# Lighting.net
KiCad netlist of a schematic drawn in EAGLE
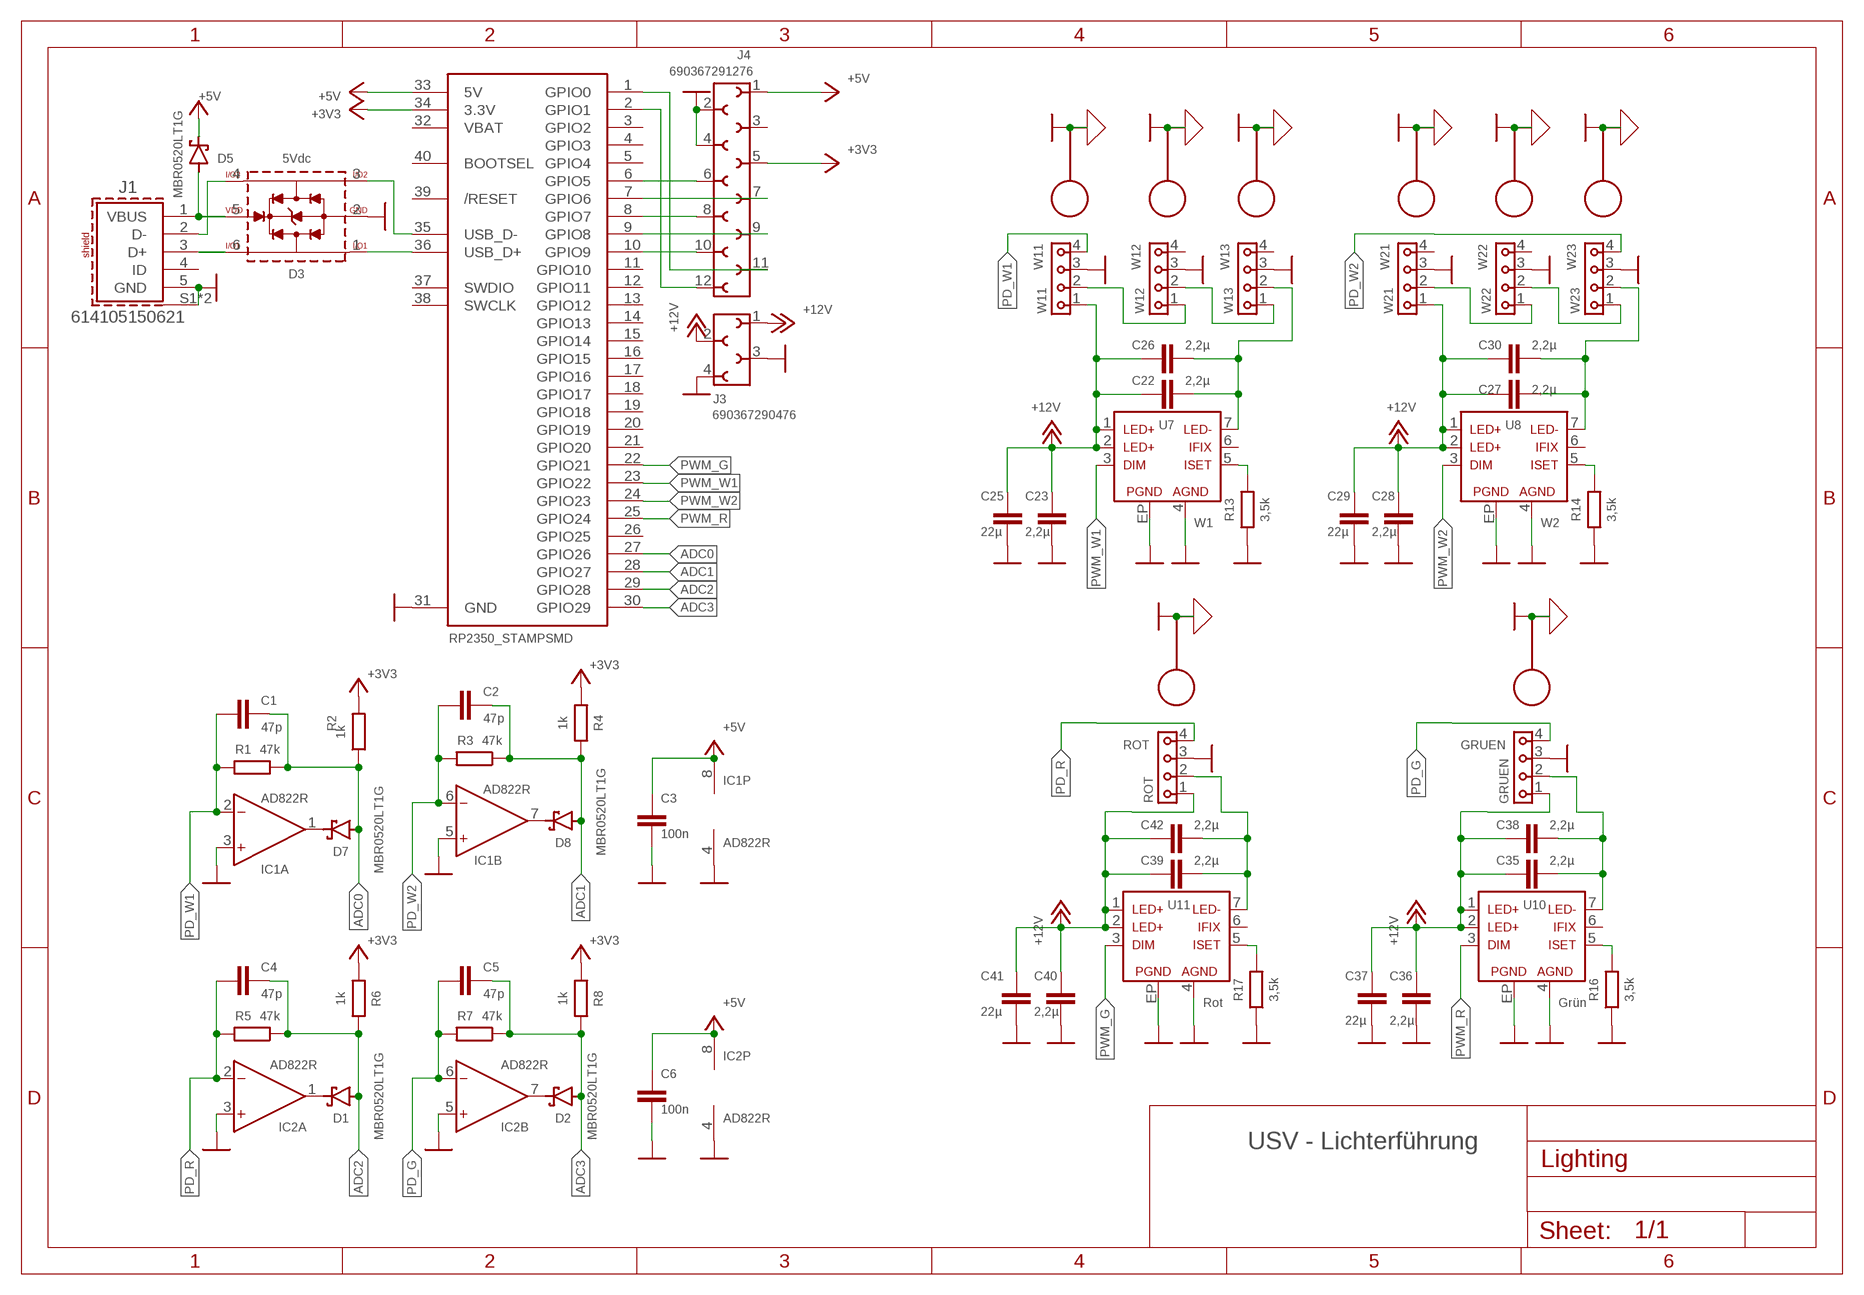
[diagram p0: schematic, sheet 1]

(export (version "E")
  (design (tool "Eeschema 10.0.6"))
  (components
    (comp (ref "C1")
      (value "47p")
      (footprint "eagle-import:CAPC2012X110")
      (libsource (lib "eagle-import") (part "CCHIP-0805(2012-METRIC)_"))
    )
    (comp (ref "C2")
      (value "47p")
      (footprint "eagle-import:CAPC2012X110")
      (libsource (lib "eagle-import") (part "CCHIP-0805(2012-METRIC)_"))
    )
    (comp (ref "C3")
      (value "100n")
      (footprint "eagle-import:CAPC2012X110")
      (libsource (lib "eagle-import") (part "CCHIP-0805(2012-METRIC)_"))
    )
    (comp (ref "C4")
      (value "47p")
      (footprint "eagle-import:CAPC2012X110")
      (libsource (lib "eagle-import") (part "CCHIP-0805(2012-METRIC)_"))
    )
    (comp (ref "C5")
      (value "47p")
      (footprint "eagle-import:CAPC2012X110")
      (libsource (lib "eagle-import") (part "CCHIP-0805(2012-METRIC)_"))
    )
    (comp (ref "C6")
      (value "100n")
      (footprint "eagle-import:CAPC2012X110")
      (libsource (lib "eagle-import") (part "CCHIP-0805(2012-METRIC)_"))
    )
    (comp (ref "C22")
      (value "2,2µ")
      (footprint "eagle-import:CAPC2012X110")
      (libsource (lib "eagle-import") (part "CCHIP-0805(2012-METRIC)_"))
    )
    (comp (ref "C23")
      (value "2,2µ")
      (footprint "eagle-import:CAPC2012X110")
      (libsource (lib "eagle-import") (part "CCHIP-0805(2012-METRIC)_"))
    )
    (comp (ref "C25")
      (value "22µ")
      (footprint "eagle-import:CAPC2012X110")
      (libsource (lib "eagle-import") (part "CCHIP-0805(2012-METRIC)_"))
    )
    (comp (ref "C26")
      (value "2,2µ")
      (footprint "eagle-import:CAPC2012X110")
      (libsource (lib "eagle-import") (part "CCHIP-0805(2012-METRIC)_"))
    )
    (comp (ref "C27")
      (value "2,2µ")
      (footprint "eagle-import:CAPC2012X110")
      (libsource (lib "eagle-import") (part "CCHIP-0805(2012-METRIC)_"))
    )
    (comp (ref "C28")
      (value "2,2µ")
      (footprint "eagle-import:CAPC2012X110")
      (libsource (lib "eagle-import") (part "CCHIP-0805(2012-METRIC)_"))
    )
    (comp (ref "C29")
      (value "22µ")
      (footprint "eagle-import:CAPC2012X110")
      (libsource (lib "eagle-import") (part "CCHIP-0805(2012-METRIC)_"))
    )
    (comp (ref "C30")
      (value "2,2µ")
      (footprint "eagle-import:CAPC2012X110")
      (libsource (lib "eagle-import") (part "CCHIP-0805(2012-METRIC)_"))
    )
    (comp (ref "C35")
      (value "2,2µ")
      (footprint "eagle-import:CAPC2012X110")
      (libsource (lib "eagle-import") (part "CCHIP-0805(2012-METRIC)_"))
    )
    (comp (ref "C36")
      (value "2,2µ")
      (footprint "eagle-import:CAPC2012X110")
      (libsource (lib "eagle-import") (part "CCHIP-0805(2012-METRIC)_"))
    )
    (comp (ref "C37")
      (value "22µ")
      (footprint "eagle-import:CAPC2012X110")
      (libsource (lib "eagle-import") (part "CCHIP-0805(2012-METRIC)_"))
    )
    (comp (ref "C38")
      (value "2,2µ")
      (footprint "eagle-import:CAPC2012X110")
      (libsource (lib "eagle-import") (part "CCHIP-0805(2012-METRIC)_"))
    )
    (comp (ref "C39")
      (value "2,2µ")
      (footprint "eagle-import:CAPC2012X110")
      (libsource (lib "eagle-import") (part "CCHIP-0805(2012-METRIC)_"))
    )
    (comp (ref "C40")
      (value "2,2µ")
      (footprint "eagle-import:CAPC2012X110")
      (libsource (lib "eagle-import") (part "CCHIP-0805(2012-METRIC)_"))
    )
    (comp (ref "C41")
      (value "22µ")
      (footprint "eagle-import:CAPC2012X110")
      (libsource (lib "eagle-import") (part "CCHIP-0805(2012-METRIC)_"))
    )
    (comp (ref "C42")
      (value "2,2µ")
      (footprint "eagle-import:CAPC2012X110")
      (libsource (lib "eagle-import") (part "CCHIP-0805(2012-METRIC)_"))
    )
    (comp (ref "D1")
      (value "MBR0520LT1G")
      (footprint "eagle-import:SODFL3718X115")
      (fields (field (name "MANUFACTURER") "ON Semiconductor"))
      (libsource (lib "eagle-import") (part "SCHOTTKY_DO-219MBR0520LT1G"))
    )
    (comp (ref "D2")
      (value "MBR0520LT1G")
      (footprint "eagle-import:SODFL3718X115")
      (fields (field (name "MANUFACTURER") "ON Semiconductor"))
      (libsource (lib "eagle-import") (part "SCHOTTKY_DO-219MBR0520LT1G"))
    )
    (comp (ref "D3")
      (value "5Vdc")
      (footprint "eagle-import:WE-TVS_SOT563")
      (libsource (lib "eagle-import") (part "WE-TVS-HS_SOT563_82400152"))
    )
    (comp (ref "D5")
      (value "MBR0520LT1G")
      (footprint "eagle-import:SODFL3718X115")
      (fields (field (name "MANUFACTURER") "ON Semiconductor"))
      (libsource (lib "eagle-import") (part "SCHOTTKY_DO-219MBR0520LT1G"))
    )
    (comp (ref "D7")
      (value "MBR0520LT1G")
      (footprint "eagle-import:SODFL3718X115")
      (fields (field (name "MANUFACTURER") "ON Semiconductor"))
      (libsource (lib "eagle-import") (part "SCHOTTKY_DO-219MBR0520LT1G"))
    )
    (comp (ref "D8")
      (value "MBR0520LT1G")
      (footprint "eagle-import:SODFL3718X115")
      (fields (field (name "MANUFACTURER") "ON Semiconductor"))
      (libsource (lib "eagle-import") (part "SCHOTTKY_DO-219MBR0520LT1G"))
    )
    (comp (ref "GRUEN")
      (value "GRUEN")
      (footprint "eagle-import:LED_PLATINE")
      (libsource (lib "eagle-import") (part "LED_PLATINE"))
    )
    (comp (ref "IC1")
      (value "AD822R")
      (footprint "eagle-import:SO8")
      (fields (field (name "MF") "ANALOG DEVICES") (field (name "MPN") "AD822BRZ"))
      (libsource (lib "eagle-import") (part "AD822R"))
    )
    (comp (ref "IC2")
      (value "AD822R")
      (footprint "eagle-import:SO8")
      (fields (field (name "MF") "ANALOG DEVICES") (field (name "MPN") "AD822BRZ"))
      (libsource (lib "eagle-import") (part "AD822R"))
    )
    (comp (ref "J1")
      (value "614105150621")
      (footprint "eagle-import:614105150621")
      (libsource (lib "eagle-import") (part "614105150621"))
    )
    (comp (ref "J3")
      (value "690367290476")
      (footprint "eagle-import:690367290476")
      (libsource (lib "eagle-import") (part "690367290476"))
    )
    (comp (ref "J4")
      (value "690367291276")
      (footprint "eagle-import:690367291276")
      (libsource (lib "eagle-import") (part "690367291276"))
    )
    (comp (ref "R1")
      (value "47k")
      (footprint "eagle-import:RESC2012X65")
      (libsource (lib "eagle-import") (part "RCHIP-0805(2012-METRIC)_"))
    )
    (comp (ref "R2")
      (value "1k")
      (footprint "eagle-import:RESC2012X65")
      (libsource (lib "eagle-import") (part "RCHIP-0805(2012-METRIC)_"))
    )
    (comp (ref "R3")
      (value "47k")
      (footprint "eagle-import:RESC2012X65")
      (libsource (lib "eagle-import") (part "RCHIP-0805(2012-METRIC)_"))
    )
    (comp (ref "R4")
      (value "1k")
      (footprint "eagle-import:RESC2012X65")
      (libsource (lib "eagle-import") (part "RCHIP-0805(2012-METRIC)_"))
    )
    (comp (ref "R5")
      (value "47k")
      (footprint "eagle-import:RESC2012X65")
      (libsource (lib "eagle-import") (part "RCHIP-0805(2012-METRIC)_"))
    )
    (comp (ref "R6")
      (value "1k")
      (footprint "eagle-import:RESC2012X65")
      (libsource (lib "eagle-import") (part "RCHIP-0805(2012-METRIC)_"))
    )
    (comp (ref "R7")
      (value "47k")
      (footprint "eagle-import:RESC2012X65")
      (libsource (lib "eagle-import") (part "RCHIP-0805(2012-METRIC)_"))
    )
    (comp (ref "R8")
      (value "1k")
      (footprint "eagle-import:RESC2012X65")
      (libsource (lib "eagle-import") (part "RCHIP-0805(2012-METRIC)_"))
    )
    (comp (ref "R13")
      (value "3,5k")
      (footprint "eagle-import:RESC2012X65")
      (libsource (lib "eagle-import") (part "RCHIP-0805(2012-METRIC)_"))
    )
    (comp (ref "R14")
      (value "3,5k")
      (footprint "eagle-import:RESC2012X65")
      (libsource (lib "eagle-import") (part "RCHIP-0805(2012-METRIC)_"))
    )
    (comp (ref "R16")
      (value "3,5k")
      (footprint "eagle-import:RESC2012X65")
      (libsource (lib "eagle-import") (part "RCHIP-0805(2012-METRIC)_"))
    )
    (comp (ref "R17")
      (value "3,5k")
      (footprint "eagle-import:RESC2012X65")
      (libsource (lib "eagle-import") (part "RCHIP-0805(2012-METRIC)_"))
    )
    (comp (ref "ROT")
      (value "ROT")
      (footprint "eagle-import:LED_PLATINE")
      (libsource (lib "eagle-import") (part "LED_PLATINE"))
    )
    (comp (ref "U$1")
      (value "RP2350_STAMPSMD")
      (footprint "eagle-import:RP2XXX_STAMP_SMD")
      (libsource (lib "eagle-import") (part "RP2350_STAMPSMD"))
    )
    (comp (ref "U7")
      (value "W1")
      (footprint "eagle-import:MAGI³C-LDHM_172946001")
      (libsource (lib "eagle-import") (part "MAGI³C-LDHM_172946001"))
    )
    (comp (ref "U8")
      (value "W2")
      (footprint "eagle-import:MAGI³C-LDHM_172946001")
      (libsource (lib "eagle-import") (part "MAGI³C-LDHM_172946001"))
    )
    (comp (ref "U10")
      (value "Grün")
      (footprint "eagle-import:MAGI³C-LDHM_172946001")
      (libsource (lib "eagle-import") (part "MAGI³C-LDHM_172946001"))
    )
    (comp (ref "U11")
      (value "Rot")
      (footprint "eagle-import:MAGI³C-LDHM_172946001")
      (libsource (lib "eagle-import") (part "MAGI³C-LDHM_172946001"))
    )
    (comp (ref "W11")
      (value "W11")
      (footprint "eagle-import:LED_PLATINE")
      (libsource (lib "eagle-import") (part "LED_PLATINE"))
    )
    (comp (ref "W12")
      (value "W12")
      (footprint "eagle-import:LED_PLATINE")
      (libsource (lib "eagle-import") (part "LED_PLATINE"))
    )
    (comp (ref "W13")
      (value "W13")
      (footprint "eagle-import:LED_PLATINE")
      (libsource (lib "eagle-import") (part "LED_PLATINE"))
    )
    (comp (ref "W21")
      (value "W21")
      (footprint "eagle-import:LED_PLATINE")
      (libsource (lib "eagle-import") (part "LED_PLATINE"))
    )
    (comp (ref "W22")
      (value "W22")
      (footprint "eagle-import:LED_PLATINE")
      (libsource (lib "eagle-import") (part "LED_PLATINE"))
    )
    (comp (ref "W23")
      (value "W23")
      (footprint "eagle-import:LED_PLATINE")
      (libsource (lib "eagle-import") (part "LED_PLATINE"))
    )
  )
  (nets
    (net (code "1") (name "+3V3") (class "Default")
      (node (ref "J4") (pin "5") (pinfunction "5_5") (pintype "passive"))
      (node (ref "R2") (pin "2") (pinfunction "2_2") (pintype "passive"))
      (node (ref "R4") (pin "2") (pinfunction "2_2") (pintype "passive"))
      (node (ref "R6") (pin "2") (pinfunction "2_2") (pintype "passive"))
      (node (ref "R8") (pin "2") (pinfunction "2_2") (pintype "passive"))
      (node (ref "U$1") (pin "34") (pinfunction "3.3V_34") (pintype "power_in"))
    )
    (net (code "2") (name "+5V") (class "Default")
      (node (ref "C3") (pin "1") (pinfunction "1_1") (pintype "passive"))
      (node (ref "C6") (pin "1") (pinfunction "1_1") (pintype "passive"))
      (node (ref "D5") (pin "1") (pinfunction "C_1") (pintype "passive"))
      (node (ref "IC1") (pin "8") (pinfunction "V+_8") (pintype "power_in"))
      (node (ref "IC2") (pin "8") (pinfunction "V+_8") (pintype "power_in"))
      (node (ref "J4") (pin "1") (pinfunction "1_1") (pintype "passive"))
      (node (ref "U$1") (pin "33") (pinfunction "5V_33") (pintype "power_in"))
    )
    (net (code "3") (name "+12V") (class "Default")
      (node (ref "C22") (pin "1") (pinfunction "1_1") (pintype "passive"))
      (node (ref "C23") (pin "1") (pinfunction "1_1") (pintype "passive"))
      (node (ref "C25") (pin "1") (pinfunction "1_1") (pintype "passive"))
      (node (ref "C26") (pin "1") (pinfunction "1_1") (pintype "passive"))
      (node (ref "C27") (pin "1") (pinfunction "1_1") (pintype "passive"))
      (node (ref "C28") (pin "1") (pinfunction "1_1") (pintype "passive"))
      (node (ref "C29") (pin "1") (pinfunction "1_1") (pintype "passive"))
      (node (ref "C30") (pin "1") (pinfunction "1_1") (pintype "passive"))
      (node (ref "C35") (pin "1") (pinfunction "1_1") (pintype "passive"))
      (node (ref "C36") (pin "1") (pinfunction "1_1") (pintype "passive"))
      (node (ref "C37") (pin "1") (pinfunction "1_1") (pintype "passive"))
      (node (ref "C38") (pin "1") (pinfunction "1_1") (pintype "passive"))
      (node (ref "C39") (pin "1") (pinfunction "1_1") (pintype "passive"))
      (node (ref "C40") (pin "1") (pinfunction "1_1") (pintype "passive"))
      (node (ref "C41") (pin "1") (pinfunction "1_1") (pintype "passive"))
      (node (ref "C42") (pin "1") (pinfunction "1_1") (pintype "passive"))
      (node (ref "GRUEN") (pin "1") (pinfunction "1_1") (pintype "passive"))
      (node (ref "J3") (pin "1") (pinfunction "1_1") (pintype "passive"))
      (node (ref "J3") (pin "2") (pinfunction "2_2") (pintype "passive"))
      (node (ref "ROT") (pin "1") (pinfunction "1_1") (pintype "passive"))
      (node (ref "U10") (pin "1") (pinfunction "LED+_1") (pintype "power_in"))
      (node (ref "U10") (pin "2") (pinfunction "LED1+_2") (pintype "power_in"))
      (node (ref "U11") (pin "1") (pinfunction "LED+_1") (pintype "power_in"))
      (node (ref "U11") (pin "2") (pinfunction "LED1+_2") (pintype "power_in"))
      (node (ref "U7") (pin "1") (pinfunction "LED+_1") (pintype "power_in"))
      (node (ref "U7") (pin "2") (pinfunction "LED1+_2") (pintype "power_in"))
      (node (ref "U8") (pin "1") (pinfunction "LED+_1") (pintype "power_in"))
      (node (ref "U8") (pin "2") (pinfunction "LED1+_2") (pintype "power_in"))
      (node (ref "W11") (pin "1") (pinfunction "1_1") (pintype "passive"))
      (node (ref "W21") (pin "1") (pinfunction "1_1") (pintype "passive"))
    )
    (net (code "4") (name "/VBAT") (class "Default")
      (node (ref "U$1") (pin "32") (pinfunction "VBAT_32") (pintype "power_in"))
    )
    (net (code "5") (name "ADC0") (class "Default")
      (node (ref "C1") (pin "2") (pinfunction "2_2") (pintype "passive"))
      (node (ref "D7") (pin "2") (pinfunction "A_2") (pintype "passive"))
      (node (ref "R1") (pin "1") (pinfunction "1_1") (pintype "passive"))
      (node (ref "R2") (pin "1") (pinfunction "1_1") (pintype "passive"))
      (node (ref "U$1") (pin "27") (pinfunction "GPIO26_27") (pintype "bidirectional"))
    )
    (net (code "6") (name "ADC1") (class "Default")
      (node (ref "C2") (pin "2") (pinfunction "2_2") (pintype "passive"))
      (node (ref "D8") (pin "2") (pinfunction "A_2") (pintype "passive"))
      (node (ref "R3") (pin "1") (pinfunction "1_1") (pintype "passive"))
      (node (ref "R4") (pin "1") (pinfunction "1_1") (pintype "passive"))
      (node (ref "U$1") (pin "28") (pinfunction "GPIO27_28") (pintype "bidirectional"))
    )
    (net (code "7") (name "ADC2") (class "Default")
      (node (ref "C4") (pin "2") (pinfunction "2_2") (pintype "passive"))
      (node (ref "D1") (pin "2") (pinfunction "A_2") (pintype "passive"))
      (node (ref "R5") (pin "1") (pinfunction "1_1") (pintype "passive"))
      (node (ref "R6") (pin "1") (pinfunction "1_1") (pintype "passive"))
      (node (ref "U$1") (pin "29") (pinfunction "GPIO28_29") (pintype "bidirectional"))
    )
    (net (code "8") (name "ADC3") (class "Default")
      (node (ref "C5") (pin "2") (pinfunction "2_2") (pintype "passive"))
      (node (ref "D2") (pin "2") (pinfunction "A_2") (pintype "passive"))
      (node (ref "R7") (pin "1") (pinfunction "1_1") (pintype "passive"))
      (node (ref "R8") (pin "1") (pinfunction "1_1") (pintype "passive"))
      (node (ref "U$1") (pin "30") (pinfunction "GPIO29_30") (pintype "bidirectional"))
    )
    (net (code "9") (name "GND") (class "Default")
      (node (ref "C23") (pin "2") (pinfunction "2_2") (pintype "passive"))
      (node (ref "C25") (pin "2") (pinfunction "2_2") (pintype "passive"))
      (node (ref "C28") (pin "2") (pinfunction "2_2") (pintype "passive"))
      (node (ref "C29") (pin "2") (pinfunction "2_2") (pintype "passive"))
      (node (ref "C3") (pin "2") (pinfunction "2_2") (pintype "passive"))
      (node (ref "C36") (pin "2") (pinfunction "2_2") (pintype "passive"))
      (node (ref "C37") (pin "2") (pinfunction "2_2") (pintype "passive"))
      (node (ref "C40") (pin "2") (pinfunction "2_2") (pintype "passive"))
      (node (ref "C41") (pin "2") (pinfunction "2_2") (pintype "passive"))
      (node (ref "C6") (pin "2") (pinfunction "2_2") (pintype "passive"))
      (node (ref "D3") (pin "2") (pinfunction "GND_2") (pintype "passive"))
      (node (ref "GRUEN") (pin "3") (pinfunction "3_3") (pintype "passive"))
      (node (ref "GRUEN") (pin "5") (pinfunction "5_5") (pintype "power_in"))
      (node (ref "IC1") (pin "3") (pinfunction "IN+_3") (pintype "input"))
      (node (ref "IC1") (pin "4") (pinfunction "V-_4") (pintype "power_in"))
      (node (ref "IC1") (pin "5") (pinfunction "IN+_5") (pintype "input"))
      (node (ref "IC2") (pin "3") (pinfunction "IN+_3") (pintype "input"))
      (node (ref "IC2") (pin "4") (pinfunction "V-_4") (pintype "power_in"))
      (node (ref "IC2") (pin "5") (pinfunction "IN+_5") (pintype "input"))
      (node (ref "J1") (pin "5") (pinfunction "GND_5") (pintype "passive"))
      (node (ref "J1") (pin "S1") (pinfunction "SHIELD_S1") (pintype "passive"))
      (node (ref "J1") (pin "S2") (pinfunction "SHIELD_S2") (pintype "passive"))
      (node (ref "J3") (pin "3") (pinfunction "3_3") (pintype "passive"))
      (node (ref "J3") (pin "4") (pinfunction "4_4") (pintype "passive"))
      (node (ref "J4") (pin "2") (pinfunction "2_2") (pintype "passive"))
      (node (ref "J4") (pin "4") (pinfunction "4_4") (pintype "passive"))
      (node (ref "R13") (pin "1") (pinfunction "1_1") (pintype "passive"))
      (node (ref "R14") (pin "1") (pinfunction "1_1") (pintype "passive"))
      (node (ref "R16") (pin "1") (pinfunction "1_1") (pintype "passive"))
      (node (ref "R17") (pin "1") (pinfunction "1_1") (pintype "passive"))
      (node (ref "ROT") (pin "3") (pinfunction "3_3") (pintype "passive"))
      (node (ref "ROT") (pin "5") (pinfunction "5_5") (pintype "power_in"))
      (node (ref "U$1") (pin "31") (pinfunction "GND_31") (pintype "power_in"))
      (node (ref "U10") (pin "4") (pinfunction "AGND_4") (pintype "power_in"))
      (node (ref "U10") (pin "EP") (pinfunction "PGND_EP") (pintype "power_in"))
      (node (ref "U11") (pin "4") (pinfunction "AGND_4") (pintype "power_in"))
      (node (ref "U11") (pin "EP") (pinfunction "PGND_EP") (pintype "power_in"))
      (node (ref "U7") (pin "4") (pinfunction "AGND_4") (pintype "power_in"))
      (node (ref "U7") (pin "EP") (pinfunction "PGND_EP") (pintype "power_in"))
      (node (ref "U8") (pin "4") (pinfunction "AGND_4") (pintype "power_in"))
      (node (ref "U8") (pin "EP") (pinfunction "PGND_EP") (pintype "power_in"))
      (node (ref "W11") (pin "3") (pinfunction "3_3") (pintype "passive"))
      (node (ref "W11") (pin "5") (pinfunction "5_5") (pintype "power_in"))
      (node (ref "W12") (pin "3") (pinfunction "3_3") (pintype "passive"))
      (node (ref "W12") (pin "5") (pinfunction "5_5") (pintype "power_in"))
      (node (ref "W13") (pin "3") (pinfunction "3_3") (pintype "passive"))
      (node (ref "W13") (pin "5") (pinfunction "5_5") (pintype "power_in"))
      (node (ref "W21") (pin "3") (pinfunction "3_3") (pintype "passive"))
      (node (ref "W21") (pin "5") (pinfunction "5_5") (pintype "power_in"))
      (node (ref "W22") (pin "3") (pinfunction "3_3") (pintype "passive"))
      (node (ref "W22") (pin "5") (pinfunction "5_5") (pintype "power_in"))
      (node (ref "W23") (pin "3") (pinfunction "3_3") (pintype "passive"))
      (node (ref "W23") (pin "5") (pinfunction "5_5") (pintype "power_in"))
    )
    (net (code "10") (name "Net-(D1-C)") (class "Default")
      (node (ref "D1") (pin "1") (pinfunction "C_1") (pintype "passive"))
      (node (ref "IC2") (pin "1") (pinfunction "OUT_1") (pintype "output"))
    )
    (net (code "11") (name "Net-(D2-C)") (class "Default")
      (node (ref "D2") (pin "1") (pinfunction "C_1") (pintype "passive"))
      (node (ref "IC2") (pin "7") (pinfunction "OUT_7") (pintype "output"))
    )
    (net (code "12") (name "Net-(D3-I{slash}O1)") (class "Default")
      (node (ref "D3") (pin "1") (pinfunction "I/O1_1") (pintype "passive"))
      (node (ref "U$1") (pin "36") (pinfunction "USB_D+_36") (pintype "bidirectional"))
    )
    (net (code "13") (name "Net-(D3-I{slash}O2)") (class "Default")
      (node (ref "D3") (pin "3") (pinfunction "I/O2_3") (pintype "passive"))
      (node (ref "U$1") (pin "35") (pinfunction "USB_D-_35") (pintype "bidirectional"))
    )
    (net (code "14") (name "Net-(D3-I{slash}O3)") (class "Default")
      (node (ref "D3") (pin "6") (pinfunction "I/O3_6") (pintype "passive"))
      (node (ref "J1") (pin "3") (pinfunction "D+_3") (pintype "passive"))
    )
    (net (code "15") (name "Net-(D3-I{slash}O4)") (class "Default")
      (node (ref "D3") (pin "4") (pinfunction "I/O4_4") (pintype "passive"))
      (node (ref "J1") (pin "2") (pinfunction "D-_2") (pintype "passive"))
    )
    (net (code "16") (name "Net-(D3-VDD)") (class "Default")
      (node (ref "D3") (pin "5") (pinfunction "VDD_5") (pintype "passive"))
      (node (ref "D5") (pin "2") (pinfunction "A_2") (pintype "passive"))
      (node (ref "J1") (pin "1") (pinfunction "VBUS_1") (pintype "passive"))
    )
    (net (code "17") (name "Net-(D7-C)") (class "Default")
      (node (ref "D7") (pin "1") (pinfunction "C_1") (pintype "passive"))
      (node (ref "IC1") (pin "1") (pinfunction "OUT_1") (pintype "output"))
    )
    (net (code "18") (name "Net-(D8-C)") (class "Default")
      (node (ref "D8") (pin "1") (pinfunction "C_1") (pintype "passive"))
      (node (ref "IC1") (pin "7") (pinfunction "OUT_7") (pintype "output"))
    )
    (net (code "19") (name "Net-(U$1-GPIO0)") (class "Default")
      (node (ref "J4") (pin "11") (pinfunction "11_11") (pintype "passive"))
      (node (ref "U$1") (pin "1") (pinfunction "GPIO0_1") (pintype "bidirectional"))
    )
    (net (code "20") (name "Net-(U$1-GPIO1)") (class "Default")
      (node (ref "J4") (pin "12") (pinfunction "12_12") (pintype "passive"))
      (node (ref "U$1") (pin "2") (pinfunction "GPIO1_2") (pintype "bidirectional"))
    )
    (net (code "21") (name "Net-(U$1-GPIO5)") (class "Default")
      (node (ref "J4") (pin "6") (pinfunction "6_6") (pintype "passive"))
      (node (ref "U$1") (pin "6") (pinfunction "GPIO5_6") (pintype "bidirectional"))
    )
    (net (code "22") (name "Net-(U$1-GPIO6)") (class "Default")
      (node (ref "J4") (pin "7") (pinfunction "7_7") (pintype "passive"))
      (node (ref "U$1") (pin "7") (pinfunction "GPIO6_7") (pintype "bidirectional"))
    )
    (net (code "23") (name "Net-(U$1-GPIO7)") (class "Default")
      (node (ref "J4") (pin "8") (pinfunction "8_8") (pintype "passive"))
      (node (ref "U$1") (pin "8") (pinfunction "GPIO7_8") (pintype "bidirectional"))
    )
    (net (code "24") (name "Net-(U$1-GPIO8)") (class "Default")
      (node (ref "J4") (pin "9") (pinfunction "9_9") (pintype "passive"))
      (node (ref "U$1") (pin "9") (pinfunction "GPIO8_9") (pintype "bidirectional"))
    )
    (net (code "25") (name "Net-(U$1-GPIO9)") (class "Default")
      (node (ref "J4") (pin "10") (pinfunction "10_10") (pintype "passive"))
      (node (ref "U$1") (pin "10") (pinfunction "GPIO9_10") (pintype "bidirectional"))
    )
    (net (code "26") (name "Net-(U7-ISET)") (class "Default")
      (node (ref "R13") (pin "2") (pinfunction "2_2") (pintype "passive"))
      (node (ref "U7") (pin "5") (pinfunction "ISET_5") (pintype "input"))
    )
    (net (code "27") (name "Net-(U7-LED-)") (class "Default")
      (node (ref "C22") (pin "2") (pinfunction "2_2") (pintype "passive"))
      (node (ref "C26") (pin "2") (pinfunction "2_2") (pintype "passive"))
      (node (ref "U7") (pin "7") (pinfunction "LED-_7") (pintype "input"))
      (node (ref "W13") (pin "2") (pinfunction "2_2") (pintype "passive"))
    )
    (net (code "28") (name "Net-(U8-ISET)") (class "Default")
      (node (ref "R14") (pin "2") (pinfunction "2_2") (pintype "passive"))
      (node (ref "U8") (pin "5") (pinfunction "ISET_5") (pintype "input"))
    )
    (net (code "29") (name "Net-(U8-LED-)") (class "Default")
      (node (ref "C27") (pin "2") (pinfunction "2_2") (pintype "passive"))
      (node (ref "C30") (pin "2") (pinfunction "2_2") (pintype "passive"))
      (node (ref "U8") (pin "7") (pinfunction "LED-_7") (pintype "input"))
      (node (ref "W23") (pin "2") (pinfunction "2_2") (pintype "passive"))
    )
    (net (code "30") (name "Net-(U10-ISET)") (class "Default")
      (node (ref "R16") (pin "2") (pinfunction "2_2") (pintype "passive"))
      (node (ref "U10") (pin "5") (pinfunction "ISET_5") (pintype "input"))
    )
    (net (code "31") (name "Net-(U10-LED-)") (class "Default")
      (node (ref "C35") (pin "2") (pinfunction "2_2") (pintype "passive"))
      (node (ref "C38") (pin "2") (pinfunction "2_2") (pintype "passive"))
      (node (ref "GRUEN") (pin "2") (pinfunction "2_2") (pintype "passive"))
      (node (ref "U10") (pin "7") (pinfunction "LED-_7") (pintype "input"))
    )
    (net (code "32") (name "Net-(U11-ISET)") (class "Default")
      (node (ref "R17") (pin "2") (pinfunction "2_2") (pintype "passive"))
      (node (ref "U11") (pin "5") (pinfunction "ISET_5") (pintype "input"))
    )
    (net (code "33") (name "Net-(U11-LED-)") (class "Default")
      (node (ref "C39") (pin "2") (pinfunction "2_2") (pintype "passive"))
      (node (ref "C42") (pin "2") (pinfunction "2_2") (pintype "passive"))
      (node (ref "ROT") (pin "2") (pinfunction "2_2") (pintype "passive"))
      (node (ref "U11") (pin "7") (pinfunction "LED-_7") (pintype "input"))
    )
    (net (code "34") (name "Net-(W11-Pad2)") (class "Default")
      (node (ref "W11") (pin "2") (pinfunction "2_2") (pintype "passive"))
      (node (ref "W12") (pin "1") (pinfunction "1_1") (pintype "passive"))
    )
    (net (code "35") (name "Net-(W12-Pad2)") (class "Default")
      (node (ref "W12") (pin "2") (pinfunction "2_2") (pintype "passive"))
      (node (ref "W13") (pin "1") (pinfunction "1_1") (pintype "passive"))
    )
    (net (code "36") (name "Net-(W21-Pad2)") (class "Default")
      (node (ref "W21") (pin "2") (pinfunction "2_2") (pintype "passive"))
      (node (ref "W22") (pin "1") (pinfunction "1_1") (pintype "passive"))
    )
    (net (code "37") (name "Net-(W22-Pad2)") (class "Default")
      (node (ref "W22") (pin "2") (pinfunction "2_2") (pintype "passive"))
      (node (ref "W23") (pin "1") (pinfunction "1_1") (pintype "passive"))
    )
    (net (code "38") (name "PD_G") (class "Default")
      (node (ref "C5") (pin "1") (pinfunction "1_1") (pintype "passive"))
      (node (ref "GRUEN") (pin "4") (pinfunction "4_4") (pintype "passive"))
      (node (ref "IC2") (pin "6") (pinfunction "IN-_6") (pintype "input"))
      (node (ref "R7") (pin "2") (pinfunction "2_2") (pintype "passive"))
    )
    (net (code "39") (name "PD_R") (class "Default")
      (node (ref "C4") (pin "1") (pinfunction "1_1") (pintype "passive"))
      (node (ref "IC2") (pin "2") (pinfunction "IN-_2") (pintype "input"))
      (node (ref "R5") (pin "2") (pinfunction "2_2") (pintype "passive"))
      (node (ref "ROT") (pin "4") (pinfunction "4_4") (pintype "passive"))
    )
    (net (code "40") (name "PD_W1") (class "Default")
      (node (ref "C1") (pin "1") (pinfunction "1_1") (pintype "passive"))
      (node (ref "IC1") (pin "2") (pinfunction "IN-_2") (pintype "input"))
      (node (ref "R1") (pin "2") (pinfunction "2_2") (pintype "passive"))
      (node (ref "W11") (pin "4") (pinfunction "4_4") (pintype "passive"))
    )
    (net (code "41") (name "PD_W2") (class "Default")
      (node (ref "C2") (pin "1") (pinfunction "1_1") (pintype "passive"))
      (node (ref "IC1") (pin "6") (pinfunction "IN-_6") (pintype "input"))
      (node (ref "R3") (pin "2") (pinfunction "2_2") (pintype "passive"))
      (node (ref "W23") (pin "4") (pinfunction "4_4") (pintype "passive"))
    )
    (net (code "42") (name "PWM_G") (class "Default")
      (node (ref "U$1") (pin "22") (pinfunction "GPIO21_22") (pintype "bidirectional"))
      (node (ref "U11") (pin "3") (pinfunction "DIM_3") (pintype "input"))
    )
    (net (code "43") (name "PWM_R") (class "Default")
      (node (ref "U$1") (pin "25") (pinfunction "GPIO24_25") (pintype "bidirectional"))
      (node (ref "U10") (pin "3") (pinfunction "DIM_3") (pintype "input"))
    )
    (net (code "44") (name "PWM_W1") (class "Default")
      (node (ref "U$1") (pin "23") (pinfunction "GPIO22_23") (pintype "bidirectional"))
      (node (ref "U7") (pin "3") (pinfunction "DIM_3") (pintype "input"))
    )
    (net (code "45") (name "PWM_W2") (class "Default")
      (node (ref "U$1") (pin "24") (pinfunction "GPIO23_24") (pintype "bidirectional"))
      (node (ref "U8") (pin "3") (pinfunction "DIM_3") (pintype "input"))
    )
    (net (code "46") (name "unconnected-(J1-ID-Pad4)") (class "Default")
      (node (ref "J1") (pin "4") (pinfunction "ID_4") (pintype "passive"))
    )
    (net (code "47") (name "unconnected-(J4-Pad3)") (class "Default")
      (node (ref "J4") (pin "3") (pinfunction "3_3") (pintype "passive"))
    )
    (net (code "48") (name "unconnected-(U$1-BOOTSEL-Pad40)") (class "Default")
      (node (ref "U$1") (pin "40") (pinfunction "BOOTSEL_40") (pintype "input"))
    )
    (net (code "49") (name "unconnected-(U$1-GPIO2-Pad3)") (class "Default")
      (node (ref "U$1") (pin "3") (pinfunction "GPIO2_3") (pintype "bidirectional"))
    )
    (net (code "50") (name "unconnected-(U$1-GPIO3-Pad4)") (class "Default")
      (node (ref "U$1") (pin "4") (pinfunction "GPIO3_4") (pintype "bidirectional"))
    )
    (net (code "51") (name "unconnected-(U$1-GPIO4-Pad5)") (class "Default")
      (node (ref "U$1") (pin "5") (pinfunction "GPIO4_5") (pintype "bidirectional"))
    )
    (net (code "52") (name "unconnected-(U$1-GPIO10-Pad11)") (class "Default")
      (node (ref "U$1") (pin "11") (pinfunction "GPIO10_11") (pintype "bidirectional"))
    )
    (net (code "53") (name "unconnected-(U$1-GPIO11-Pad12)") (class "Default")
      (node (ref "U$1") (pin "12") (pinfunction "GPIO11_12") (pintype "bidirectional"))
    )
    (net (code "54") (name "unconnected-(U$1-GPIO12-Pad13)") (class "Default")
      (node (ref "U$1") (pin "13") (pinfunction "GPIO12_13") (pintype "bidirectional"))
    )
    (net (code "55") (name "unconnected-(U$1-GPIO13-Pad14)") (class "Default")
      (node (ref "U$1") (pin "14") (pinfunction "GPIO13_14") (pintype "bidirectional"))
    )
    (net (code "56") (name "unconnected-(U$1-GPIO14-Pad15)") (class "Default")
      (node (ref "U$1") (pin "15") (pinfunction "GPIO14_15") (pintype "bidirectional"))
    )
    (net (code "57") (name "unconnected-(U$1-GPIO15-Pad16)") (class "Default")
      (node (ref "U$1") (pin "16") (pinfunction "GPIO15_16") (pintype "bidirectional"))
    )
    (net (code "58") (name "unconnected-(U$1-GPIO16-Pad17)") (class "Default")
      (node (ref "U$1") (pin "17") (pinfunction "GPIO16_17") (pintype "bidirectional"))
    )
    (net (code "59") (name "unconnected-(U$1-GPIO17-Pad18)") (class "Default")
      (node (ref "U$1") (pin "18") (pinfunction "GPIO17_18") (pintype "bidirectional"))
    )
    (net (code "60") (name "unconnected-(U$1-GPIO18-Pad19)") (class "Default")
      (node (ref "U$1") (pin "19") (pinfunction "GPIO18_19") (pintype "bidirectional"))
    )
    (net (code "61") (name "unconnected-(U$1-GPIO19-Pad20)") (class "Default")
      (node (ref "U$1") (pin "20") (pinfunction "GPIO19_20") (pintype "bidirectional"))
    )
    (net (code "62") (name "unconnected-(U$1-GPIO20-Pad21)") (class "Default")
      (node (ref "U$1") (pin "21") (pinfunction "GPIO20_21") (pintype "bidirectional"))
    )
    (net (code "63") (name "unconnected-(U$1-GPIO25-Pad26)") (class "Default")
      (node (ref "U$1") (pin "26") (pinfunction "GPIO25_26") (pintype "bidirectional"))
    )
    (net (code "64") (name "unconnected-(U$1-SWCLK-Pad38)") (class "Default")
      (node (ref "U$1") (pin "38") (pinfunction "SWCLK_38") (pintype "input"))
    )
    (net (code "65") (name "unconnected-(U$1-SWDIO-Pad37)") (class "Default")
      (node (ref "U$1") (pin "37") (pinfunction "SWDIO_37") (pintype "bidirectional"))
    )
    (net (code "66") (name "unconnected-(U$1-{slash}RESET-Pad39)") (class "Default")
      (node (ref "U$1") (pin "39") (pinfunction "/RESET_39") (pintype "bidirectional"))
    )
    (net (code "67") (name "unconnected-(U7-IFIX-Pad6)") (class "Default")
      (node (ref "U7") (pin "6") (pinfunction "IFIX_6") (pintype "input"))
    )
    (net (code "68") (name "unconnected-(U8-IFIX-Pad6)") (class "Default")
      (node (ref "U8") (pin "6") (pinfunction "IFIX_6") (pintype "input"))
    )
    (net (code "69") (name "unconnected-(U10-IFIX-Pad6)") (class "Default")
      (node (ref "U10") (pin "6") (pinfunction "IFIX_6") (pintype "input"))
    )
    (net (code "70") (name "unconnected-(U11-IFIX-Pad6)") (class "Default")
      (node (ref "U11") (pin "6") (pinfunction "IFIX_6") (pintype "input"))
    )
    (net (code "71") (name "unconnected-(W12-Pad4)") (class "Default")
      (node (ref "W12") (pin "4") (pinfunction "4_4") (pintype "passive"))
    )
    (net (code "72") (name "unconnected-(W13-Pad4)") (class "Default")
      (node (ref "W13") (pin "4") (pinfunction "4_4") (pintype "passive"))
    )
    (net (code "73") (name "unconnected-(W21-Pad4)") (class "Default")
      (node (ref "W21") (pin "4") (pinfunction "4_4") (pintype "passive"))
    )
    (net (code "74") (name "unconnected-(W22-Pad4)") (class "Default")
      (node (ref "W22") (pin "4") (pinfunction "4_4") (pintype "passive"))
    )
  )
)
